# RTC6705.net
KiCad netlist of a schematic drawn in Altium Designer
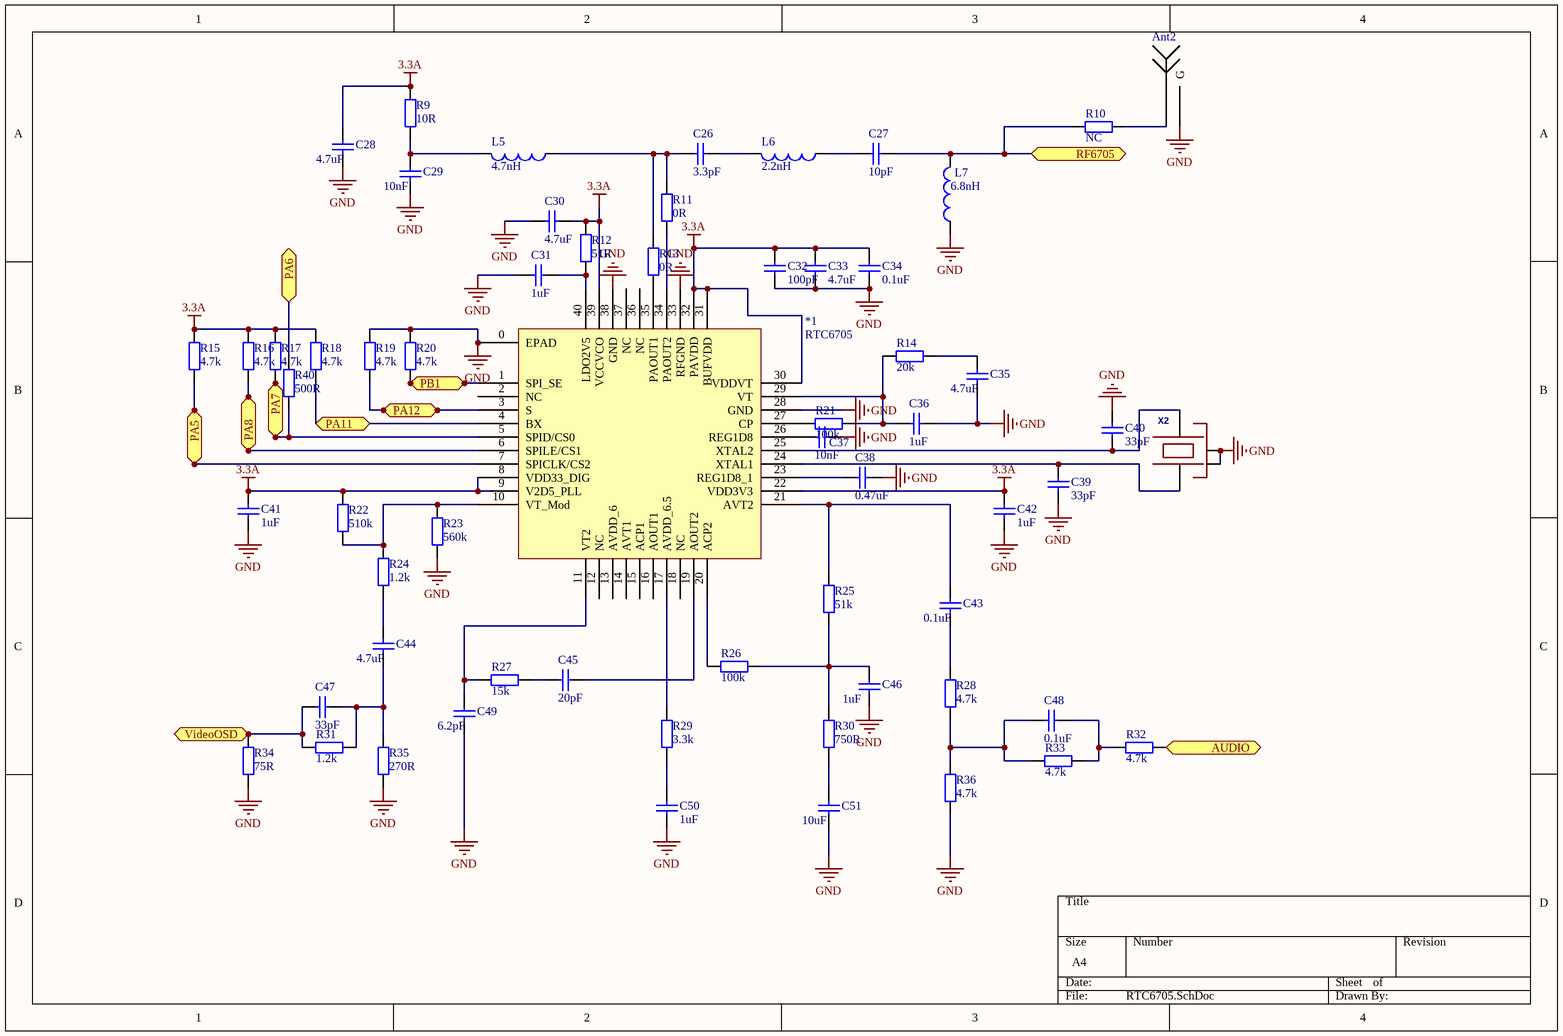
[diagram p0: RTC6705.SchDoc]

(export (version "E")
  (design (tool "Eeschema 10.0.6"))
  (components
    (comp (ref "*1") (value "RTC6705") (footprint "RTC6705") (libsource (lib "RTC6705") (part "RTC6705")))
    (comp (ref "Ant2") (value "Antenna") (footprint "SMA") (libsource (lib "RTC6705") (part "Antenna")))
    (comp (ref "C26")
      (value "3.3pF")
      (footprint "0402")
      (description "Capacitor")
      (fields (field (name "Comment") "Cap") (field (name "PUBLISHER") "Altium Limited"))
      (libsource (lib "RTC6705") (part "Cap"))
    )
    (comp (ref "C27")
      (value "10pF")
      (footprint "0402")
      (description "Capacitor")
      (fields (field (name "Comment") "Cap") (field (name "PUBLISHER") "Altium Limited"))
      (libsource (lib "RTC6705") (part "Cap"))
    )
    (comp (ref "C28")
      (value "4.7uF")
      (footprint "0603")
      (description "Capacitor")
      (fields (field (name "Comment") "Cap") (field (name "PUBLISHER") "Altium Limited"))
      (libsource (lib "RTC6705") (part "Cap"))
    )
    (comp (ref "C29")
      (value "10nF")
      (footprint "0402")
      (description "Capacitor")
      (fields (field (name "Comment") "Cap") (field (name "PUBLISHER") "Altium Limited"))
      (libsource (lib "RTC6705") (part "Cap"))
    )
    (comp (ref "C30")
      (value "4.7uF")
      (footprint "0402")
      (description "Capacitor")
      (fields (field (name "Comment") "Cap") (field (name "PUBLISHER") "Altium Limited"))
      (libsource (lib "RTC6705") (part "Cap"))
    )
    (comp (ref "C31")
      (value "1uF")
      (footprint "0402")
      (description "Capacitor")
      (fields (field (name "Comment") "Cap") (field (name "PUBLISHER") "Altium Limited"))
      (libsource (lib "RTC6705") (part "Cap"))
    )
    (comp (ref "C32")
      (value "100pF")
      (footprint "0402")
      (description "Capacitor")
      (fields (field (name "Comment") "Cap") (field (name "PUBLISHER") "Altium Limited"))
      (libsource (lib "RTC6705") (part "Cap"))
    )
    (comp (ref "C33")
      (value "4.7uF")
      (footprint "0402")
      (description "Capacitor")
      (fields (field (name "Comment") "Cap") (field (name "PUBLISHER") "Altium Limited"))
      (libsource (lib "RTC6705") (part "Cap"))
    )
    (comp (ref "C34")
      (value "0.1uF")
      (footprint "0402")
      (description "Capacitor")
      (fields (field (name "Comment") "Cap") (field (name "PUBLISHER") "Altium Limited"))
      (libsource (lib "RTC6705") (part "Cap"))
    )
    (comp (ref "C35")
      (value "4.7uF")
      (footprint "0402")
      (description "Capacitor")
      (fields (field (name "Comment") "Cap") (field (name "PUBLISHER") "Altium Limited"))
      (libsource (lib "RTC6705") (part "Cap"))
    )
    (comp (ref "C36")
      (value "1uF")
      (footprint "0402")
      (description "Capacitor")
      (fields (field (name "Comment") "Cap") (field (name "PUBLISHER") "Altium Limited"))
      (libsource (lib "RTC6705") (part "Cap"))
    )
    (comp (ref "C37")
      (value "10nF")
      (footprint "0402")
      (description "Capacitor")
      (fields (field (name "Comment") "Cap") (field (name "PUBLISHER") "Altium Limited"))
      (libsource (lib "RTC6705") (part "Cap"))
    )
    (comp (ref "C38")
      (value "0.47uF")
      (footprint "0402")
      (description "Capacitor")
      (fields (field (name "Comment") "Cap") (field (name "PUBLISHER") "Altium Limited"))
      (libsource (lib "RTC6705") (part "Cap"))
    )
    (comp (ref "C39")
      (value "33pF")
      (footprint "0402")
      (description "Capacitor")
      (fields (field (name "Comment") "Cap") (field (name "PUBLISHER") "Altium Limited"))
      (libsource (lib "RTC6705") (part "Cap"))
    )
    (comp (ref "C40")
      (value "33pF")
      (footprint "0402")
      (description "Capacitor")
      (fields (field (name "Comment") "Cap") (field (name "PUBLISHER") "Altium Limited"))
      (libsource (lib "RTC6705") (part "Cap"))
    )
    (comp (ref "C41")
      (value "1uF")
      (footprint "0402")
      (description "Capacitor")
      (fields (field (name "Comment") "Cap") (field (name "PUBLISHER") "Altium Limited"))
      (libsource (lib "RTC6705") (part "Cap"))
    )
    (comp (ref "C42")
      (value "1uF")
      (footprint "0402")
      (description "Capacitor")
      (fields (field (name "Comment") "Cap") (field (name "PUBLISHER") "Altium Limited"))
      (libsource (lib "RTC6705") (part "Cap"))
    )
    (comp (ref "C43")
      (value "0.1uF")
      (footprint "0402")
      (description "Capacitor")
      (fields (field (name "Comment") "Cap") (field (name "PUBLISHER") "Altium Limited"))
      (libsource (lib "RTC6705") (part "Cap"))
    )
    (comp (ref "C44")
      (value "4.7uF")
      (footprint "0402")
      (description "Capacitor")
      (fields (field (name "Comment") "Cap") (field (name "PUBLISHER") "Altium Limited"))
      (libsource (lib "RTC6705") (part "Cap"))
    )
    (comp (ref "C45")
      (value "20pF")
      (footprint "0402")
      (description "Capacitor")
      (fields (field (name "Comment") "Cap") (field (name "PUBLISHER") "Altium Limited"))
      (libsource (lib "RTC6705") (part "Cap"))
    )
    (comp (ref "C46")
      (value "1uF")
      (footprint "0402")
      (description "Capacitor")
      (fields (field (name "Comment") "Cap") (field (name "PUBLISHER") "Altium Limited"))
      (libsource (lib "RTC6705") (part "Cap"))
    )
    (comp (ref "C47")
      (value "33pF")
      (footprint "0402")
      (description "Capacitor")
      (fields (field (name "Comment") "Cap") (field (name "PUBLISHER") "Altium Limited"))
      (libsource (lib "RTC6705") (part "Cap"))
    )
    (comp (ref "C48")
      (value "0.1uF")
      (footprint "0402")
      (description "Capacitor")
      (fields (field (name "Comment") "Cap") (field (name "PUBLISHER") "Altium Limited"))
      (libsource (lib "RTC6705") (part "Cap"))
    )
    (comp (ref "C49")
      (value "6.2pF")
      (footprint "0402")
      (description "Capacitor")
      (fields (field (name "Comment") "Cap") (field (name "PUBLISHER") "Altium Limited"))
      (libsource (lib "RTC6705") (part "Cap"))
    )
    (comp (ref "C50")
      (value "1uF")
      (footprint "0402")
      (description "Capacitor")
      (fields (field (name "Comment") "Cap") (field (name "PUBLISHER") "Altium Limited"))
      (libsource (lib "RTC6705") (part "Cap"))
    )
    (comp (ref "C51")
      (value "10uF")
      (footprint "0402")
      (description "Capacitor")
      (fields (field (name "Comment") "Cap") (field (name "PUBLISHER") "Altium Limited"))
      (libsource (lib "RTC6705") (part "Cap"))
    )
    (comp (ref "L5")
      (value "4.7nH")
      (footprint "0402")
      (description "Inductor")
      (fields (field (name "PUBLISHER") "Altium Limited"))
      (libsource (lib "Miscellaneous Devices") (part "Inductor"))
    )
    (comp (ref "L6")
      (value "2.2nH")
      (footprint "0402")
      (description "Inductor")
      (fields (field (name "PUBLISHER") "Altium Limited"))
      (libsource (lib "Miscellaneous Devices") (part "Inductor"))
    )
    (comp (ref "L7")
      (value "6.8nH")
      (footprint "0402")
      (description "Inductor")
      (fields (field (name "PUBLISHER") "Altium Limited"))
      (libsource (lib "Miscellaneous Devices") (part "Inductor"))
    )
    (comp (ref "R9")
      (value "10R")
      (footprint "0402")
      (description "Resistor")
      (fields (field (name "Comment") "Res2") (field (name "PUBLISHER") "Altium Limited"))
      (libsource (lib "") (part "Res2_2"))
    )
    (comp (ref "R10")
      (value "NC")
      (footprint "0402")
      (description "Resistor")
      (fields (field (name "Comment") "Res2") (field (name "PUBLISHER") "Altium Limited"))
      (libsource (lib "") (part "Res2_1"))
    )
    (comp (ref "R11")
      (value "0R")
      (footprint "0402")
      (description "Resistor")
      (fields (field (name "Comment") "Res2") (field (name "PUBLISHER") "Altium Limited"))
      (libsource (lib "") (part "Res2_2"))
    )
    (comp (ref "R12")
      (value "51R")
      (footprint "0402")
      (description "Resistor")
      (fields (field (name "Comment") "Res2") (field (name "PUBLISHER") "Altium Limited"))
      (libsource (lib "") (part "Res2_2"))
    )
    (comp (ref "R13")
      (value "0R")
      (footprint "0402")
      (description "Resistor")
      (fields (field (name "Comment") "Res2") (field (name "PUBLISHER") "Altium Limited"))
      (libsource (lib "") (part "Res2_2"))
    )
    (comp (ref "R14")
      (value "20k")
      (footprint "0402")
      (description "Resistor")
      (fields (field (name "Comment") "Res2") (field (name "PUBLISHER") "Altium Limited"))
      (libsource (lib "") (part "Res2_1"))
    )
    (comp (ref "R15")
      (value "4.7k")
      (footprint "0402")
      (description "Resistor")
      (fields (field (name "Comment") "Res2") (field (name "PUBLISHER") "Altium Limited"))
      (libsource (lib "") (part "Res2_2"))
    )
    (comp (ref "R16")
      (value "4.7k")
      (footprint "0402")
      (description "Resistor")
      (fields (field (name "Comment") "Res2") (field (name "PUBLISHER") "Altium Limited"))
      (libsource (lib "") (part "Res2_2"))
    )
    (comp (ref "R17")
      (value "4.7k")
      (footprint "0402")
      (description "Resistor")
      (fields (field (name "Comment") "Res2") (field (name "PUBLISHER") "Altium Limited"))
      (libsource (lib "") (part "Res2_2"))
    )
    (comp (ref "R18")
      (value "4.7k")
      (footprint "0402")
      (description "Resistor")
      (fields (field (name "Comment") "Res2") (field (name "PUBLISHER") "Altium Limited"))
      (libsource (lib "") (part "Res2_2"))
    )
    (comp (ref "R19")
      (value "4.7k")
      (footprint "0402")
      (description "Resistor")
      (fields (field (name "Comment") "Res2") (field (name "PUBLISHER") "Altium Limited"))
      (libsource (lib "") (part "Res2_2"))
    )
    (comp (ref "R20")
      (value "4.7k")
      (footprint "0402")
      (description "Resistor")
      (fields (field (name "Comment") "Res2") (field (name "PUBLISHER") "Altium Limited"))
      (libsource (lib "") (part "Res2_2"))
    )
    (comp (ref "R21")
      (value "100k")
      (footprint "0402")
      (description "Resistor")
      (fields (field (name "Comment") "Res2") (field (name "PUBLISHER") "Altium Limited"))
      (libsource (lib "") (part "Res2_1"))
    )
    (comp (ref "R22")
      (value "510k")
      (footprint "0402")
      (description "Resistor")
      (fields (field (name "Comment") "Res2") (field (name "PUBLISHER") "Altium Limited"))
      (libsource (lib "") (part "Res2_2"))
    )
    (comp (ref "R23")
      (value "560k")
      (footprint "0402")
      (description "Resistor")
      (fields (field (name "Comment") "Res2") (field (name "PUBLISHER") "Altium Limited"))
      (libsource (lib "") (part "Res2_2"))
    )
    (comp (ref "R24")
      (value "1.2k")
      (footprint "0402")
      (description "Resistor")
      (fields (field (name "Comment") "Res2") (field (name "PUBLISHER") "Altium Limited"))
      (libsource (lib "") (part "Res2_2"))
    )
    (comp (ref "R25")
      (value "51k")
      (footprint "0402")
      (description "Resistor")
      (fields (field (name "Comment") "Res2") (field (name "PUBLISHER") "Altium Limited"))
      (libsource (lib "") (part "Res2_2"))
    )
    (comp (ref "R26")
      (value "100k")
      (footprint "0402")
      (description "Resistor")
      (fields (field (name "Comment") "Res2") (field (name "PUBLISHER") "Altium Limited"))
      (libsource (lib "") (part "Res2_1"))
    )
    (comp (ref "R27")
      (value "15k")
      (footprint "0402")
      (description "Resistor")
      (fields (field (name "Comment") "Res2") (field (name "PUBLISHER") "Altium Limited"))
      (libsource (lib "") (part "Res2_1"))
    )
    (comp (ref "R28")
      (value "4.7k")
      (footprint "0402")
      (description "Resistor")
      (fields (field (name "Comment") "Res2") (field (name "PUBLISHER") "Altium Limited"))
      (libsource (lib "") (part "Res2_2"))
    )
    (comp (ref "R29")
      (value "3.3k")
      (footprint "0402")
      (description "Resistor")
      (fields (field (name "Comment") "Res2") (field (name "PUBLISHER") "Altium Limited"))
      (libsource (lib "RTC6705") (part "Res2"))
    )
    (comp (ref "R30")
      (value "750R")
      (footprint "0402")
      (description "Resistor")
      (fields (field (name "Comment") "Res2") (field (name "PUBLISHER") "Altium Limited"))
      (libsource (lib "") (part "Res2_2"))
    )
    (comp (ref "R31")
      (value "1.2k")
      (footprint "0402")
      (description "Resistor")
      (fields (field (name "Comment") "Res2") (field (name "PUBLISHER") "Altium Limited"))
      (libsource (lib "") (part "Res2_1"))
    )
    (comp (ref "R32")
      (value "4.7k")
      (footprint "0402")
      (description "Resistor")
      (fields (field (name "Comment") "Res2") (field (name "PUBLISHER") "Altium Limited"))
      (libsource (lib "") (part "Res2_1"))
    )
    (comp (ref "R33")
      (value "4.7k")
      (footprint "0402")
      (description "Resistor")
      (fields (field (name "Comment") "Res2") (field (name "PUBLISHER") "Altium Limited"))
      (libsource (lib "") (part "Res2_1"))
    )
    (comp (ref "R34")
      (value "75R")
      (footprint "0402")
      (description "Resistor")
      (fields (field (name "Comment") "Res2") (field (name "PUBLISHER") "Altium Limited"))
      (libsource (lib "") (part "Res2_2"))
    )
    (comp (ref "R35")
      (value "270R")
      (footprint "0402")
      (description "Resistor")
      (fields (field (name "Comment") "Res2") (field (name "PUBLISHER") "Altium Limited"))
      (libsource (lib "") (part "Res2_2"))
    )
    (comp (ref "R36")
      (value "4.7k")
      (footprint "0402")
      (description "Resistor")
      (fields (field (name "Comment") "Res2") (field (name "PUBLISHER") "Altium Limited"))
      (libsource (lib "") (part "Res2_2"))
    )
    (comp (ref "R40")
      (value "500R")
      (footprint "0402")
      (description "Resistor")
      (fields (field (name "Comment") "Res2") (field (name "PUBLISHER") "Altium Limited"))
      (libsource (lib "") (part "Res2_2"))
    )
    (comp (ref "X2")
      (value "8mhz")
      (footprint "OSCILLATOR-3.2X2.5")
      (description "Crystal Oscillator in 3.2x2.5 SMD")
      (libsource (lib "pixhawk2") (part "OSCILLATOR-3.2X2.5"))
    )
  )
  (nets
    (net (code "1") (name "/AUDIO") (class "Default")
      (node (ref "R32") (pin "1") (pinfunction "1_1") (pintype "passive"))
    )
    (net (code "2") (name "/PA5") (class "Default")
      (node (ref "*1") (pin "7") (pinfunction "SPICLK/CS2_7") (pintype "passive"))
      (node (ref "R15") (pin "1") (pinfunction "1_1") (pintype "passive"))
    )
    (net (code "3") (name "/PA6") (class "Default")
      (node (ref "R40") (pin "2") (pinfunction "2_2") (pintype "passive"))
    )
    (net (code "4") (name "/PA7") (class "Default")
      (node (ref "*1") (pin "5") (pinfunction "SPID/CS0_5") (pintype "passive"))
      (node (ref "R17") (pin "1") (pinfunction "1_1") (pintype "passive"))
      (node (ref "R40") (pin "1") (pinfunction "1_1") (pintype "passive"))
    )
    (net (code "5") (name "/PA8") (class "Default")
      (node (ref "*1") (pin "6") (pinfunction "SPILE/CS1_6") (pintype "passive"))
      (node (ref "R16") (pin "1") (pinfunction "1_1") (pintype "passive"))
    )
    (net (code "6") (name "/PA11") (class "Default")
      (node (ref "*1") (pin "4") (pinfunction "BX_4") (pintype "passive"))
      (node (ref "R18") (pin "1") (pinfunction "1_1") (pintype "passive"))
    )
    (net (code "7") (name "/PA12") (class "Default")
      (node (ref "*1") (pin "3") (pinfunction "S_3") (pintype "passive"))
      (node (ref "R19") (pin "1") (pinfunction "1_1") (pintype "passive"))
    )
    (net (code "8") (name "/PB1") (class "Default")
      (node (ref "*1") (pin "1") (pinfunction "SPI_SE_1") (pintype "passive"))
      (node (ref "R20") (pin "1") (pinfunction "1_1") (pintype "passive"))
    )
    (net (code "9") (name "/RF6705") (class "Default")
      (node (ref "C27") (pin "1") (pinfunction "1_1") (pintype "passive"))
      (node (ref "L7") (pin "2") (pinfunction "2_2") (pintype "passive"))
      (node (ref "R10") (pin "2") (pinfunction "2_2") (pintype "passive"))
    )
    (net (code "10") (name "/VideoOSD") (class "Default")
      (node (ref "C47") (pin "2") (pinfunction "2_2") (pintype "passive"))
      (node (ref "R31") (pin "2") (pinfunction "2_2") (pintype "passive"))
      (node (ref "R34") (pin "2") (pinfunction "2_2") (pintype "passive"))
    )
    (net (code "11") (name "3.3A") (class "Default")
      (node (ref "*1") (pin "22") (pinfunction "VDD3V3_22") (pintype "passive"))
      (node (ref "*1") (pin "30") (pinfunction "VDDVT_30") (pintype "passive"))
      (node (ref "*1") (pin "31") (pinfunction "BUFVDD_31") (pintype "passive"))
      (node (ref "*1") (pin "32") (pinfunction "PAVDD_32") (pintype "passive"))
      (node (ref "*1") (pin "39") (pinfunction "VCCVCO_39") (pintype "passive"))
      (node (ref "*1") (pin "8") (pinfunction "VDD33_DIG_8") (pintype "passive"))
      (node (ref "*1") (pin "9") (pinfunction "V2D5_PLL_9") (pintype "passive"))
      (node (ref "C28") (pin "2") (pinfunction "2_2") (pintype "passive"))
      (node (ref "C30") (pin "2") (pinfunction "2_2") (pintype "passive"))
      (node (ref "C32") (pin "1") (pinfunction "1_1") (pintype "passive"))
      (node (ref "C33") (pin "1") (pinfunction "1_1") (pintype "passive"))
      (node (ref "C34") (pin "1") (pinfunction "1_1") (pintype "passive"))
      (node (ref "C41") (pin "1") (pinfunction "1_1") (pintype "passive"))
      (node (ref "C42") (pin "1") (pinfunction "1_1") (pintype "passive"))
      (node (ref "R12") (pin "2") (pinfunction "2_2") (pintype "passive"))
      (node (ref "R15") (pin "2") (pinfunction "2_2") (pintype "passive"))
      (node (ref "R16") (pin "2") (pinfunction "2_2") (pintype "passive"))
      (node (ref "R17") (pin "2") (pinfunction "2_2") (pintype "passive"))
      (node (ref "R18") (pin "2") (pinfunction "2_2") (pintype "passive"))
      (node (ref "R22") (pin "2") (pinfunction "2_2") (pintype "passive"))
      (node (ref "R9") (pin "2") (pinfunction "2_2") (pintype "passive"))
    )
    (net (code "12") (name "GND") (class "Default")
      (node (ref "*1") (pin "0") (pinfunction "EPAD_0") (pintype "passive"))
      (node (ref "*1") (pin "28") (pinfunction "GND_28") (pintype "passive"))
      (node (ref "*1") (pin "33") (pinfunction "RFGND_33") (pintype "passive"))
      (node (ref "*1") (pin "38") (pinfunction "GND_38") (pintype "passive"))
      (node (ref "Ant2") (pin "GND") (pinfunction "G_GND") (pintype "passive"))
      (node (ref "C28") (pin "1") (pinfunction "1_1") (pintype "passive"))
      (node (ref "C29") (pin "1") (pinfunction "1_1") (pintype "passive"))
      (node (ref "C30") (pin "1") (pinfunction "1_1") (pintype "passive"))
      (node (ref "C31") (pin "2") (pinfunction "2_2") (pintype "passive"))
      (node (ref "C32") (pin "2") (pinfunction "2_2") (pintype "passive"))
      (node (ref "C33") (pin "2") (pinfunction "2_2") (pintype "passive"))
      (node (ref "C34") (pin "2") (pinfunction "2_2") (pintype "passive"))
      (node (ref "C35") (pin "1") (pinfunction "1_1") (pintype "passive"))
      (node (ref "C36") (pin "1") (pinfunction "1_1") (pintype "passive"))
      (node (ref "C37") (pin "1") (pinfunction "1_1") (pintype "passive"))
      (node (ref "C38") (pin "1") (pinfunction "1_1") (pintype "passive"))
      (node (ref "C39") (pin "2") (pinfunction "2_2") (pintype "passive"))
      (node (ref "C40") (pin "2") (pinfunction "2_2") (pintype "passive"))
      (node (ref "C41") (pin "2") (pinfunction "2_2") (pintype "passive"))
      (node (ref "C42") (pin "2") (pinfunction "2_2") (pintype "passive"))
      (node (ref "C46") (pin "1") (pinfunction "1_1") (pintype "passive"))
      (node (ref "C49") (pin "1") (pinfunction "1_1") (pintype "passive"))
      (node (ref "C50") (pin "2") (pinfunction "2_2") (pintype "passive"))
      (node (ref "C51") (pin "1") (pinfunction "1_1") (pintype "passive"))
      (node (ref "L7") (pin "1") (pinfunction "1_1") (pintype "passive"))
      (node (ref "R19") (pin "2") (pinfunction "2_2") (pintype "passive"))
      (node (ref "R20") (pin "2") (pinfunction "2_2") (pintype "passive"))
      (node (ref "R23") (pin "1") (pinfunction "1_1") (pintype "passive"))
      (node (ref "R34") (pin "1") (pinfunction "1_1") (pintype "passive"))
      (node (ref "R35") (pin "1") (pinfunction "1_1") (pintype "passive"))
      (node (ref "R36") (pin "1") (pinfunction "1_1") (pintype "passive"))
      (node (ref "X2") (pin "2") (pinfunction "NC_2_2") (pintype "open_emitter"))
      (node (ref "X2") (pin "4") (pinfunction "NC_4_4") (pintype "open_emitter"))
    )
    (net (code "13") (name "Net-(*1-ACP2)") (class "Default")
      (node (ref "*1") (pin "20") (pinfunction "ACP2_20") (pintype "passive"))
      (node (ref "R26") (pin "2") (pinfunction "2_2") (pintype "passive"))
    )
    (net (code "14") (name "Net-(*1-AOUT2)") (class "Default")
      (node (ref "*1") (pin "19") (pinfunction "AOUT2_19") (pintype "passive"))
      (node (ref "C45") (pin "1") (pinfunction "1_1") (pintype "passive"))
    )
    (net (code "15") (name "Net-(*1-AVDD_6.5)") (class "Default")
      (node (ref "*1") (pin "17") (pinfunction "AVDD_6.5_17") (pintype "passive"))
      (node (ref "R29") (pin "1") (pinfunction "1_1") (pintype "passive"))
    )
    (net (code "16") (name "Net-(*1-AVT2)") (class "Default")
      (node (ref "*1") (pin "21") (pinfunction "AVT2_21") (pintype "passive"))
      (node (ref "C43") (pin "2") (pinfunction "2_2") (pintype "passive"))
      (node (ref "R25") (pin "2") (pinfunction "2_2") (pintype "passive"))
    )
    (net (code "17") (name "Net-(*1-CP)") (class "Default")
      (node (ref "*1") (pin "27") (pinfunction "CP_27") (pintype "passive"))
      (node (ref "R21") (pin "2") (pinfunction "2_2") (pintype "passive"))
    )
    (net (code "18") (name "Net-(*1-LDO2V5)") (class "Default")
      (node (ref "*1") (pin "40") (pinfunction "LDO2V5_40") (pintype "passive"))
      (node (ref "C31") (pin "1") (pinfunction "1_1") (pintype "passive"))
      (node (ref "R12") (pin "1") (pinfunction "1_1") (pintype "passive"))
    )
    (net (code "19") (name "Net-(*1-PAOUT1)") (class "Default")
      (node (ref "*1") (pin "35") (pinfunction "PAOUT1_35") (pintype "passive"))
      (node (ref "R13") (pin "1") (pinfunction "1_1") (pintype "passive"))
    )
    (net (code "20") (name "Net-(*1-PAOUT2)") (class "Default")
      (node (ref "*1") (pin "34") (pinfunction "PAOUT2_34") (pintype "passive"))
      (node (ref "R11") (pin "1") (pinfunction "1_1") (pintype "passive"))
    )
    (net (code "21") (name "Net-(*1-REG1D8)") (class "Default")
      (node (ref "*1") (pin "26") (pinfunction "REG1D8_26") (pintype "passive"))
      (node (ref "C37") (pin "2") (pinfunction "2_2") (pintype "passive"))
    )
    (net (code "22") (name "Net-(*1-REG1D8_1)") (class "Default")
      (node (ref "*1") (pin "23") (pinfunction "REG1D8_1_23") (pintype "passive"))
      (node (ref "C38") (pin "2") (pinfunction "2_2") (pintype "passive"))
    )
    (net (code "23") (name "Net-(*1-VT)") (class "Default")
      (node (ref "*1") (pin "29") (pinfunction "VT_29") (pintype "passive"))
      (node (ref "C36") (pin "2") (pinfunction "2_2") (pintype "passive"))
      (node (ref "R14") (pin "2") (pinfunction "2_2") (pintype "passive"))
      (node (ref "R21") (pin "1") (pinfunction "1_1") (pintype "passive"))
    )
    (net (code "24") (name "Net-(*1-VT2)") (class "Default")
      (node (ref "*1") (pin "11") (pinfunction "VT2_11") (pintype "passive"))
      (node (ref "C49") (pin "2") (pinfunction "2_2") (pintype "passive"))
      (node (ref "R27") (pin "2") (pinfunction "2_2") (pintype "passive"))
    )
    (net (code "25") (name "Net-(*1-VT_Mod)") (class "Default")
      (node (ref "*1") (pin "10") (pinfunction "VT_Mod_10") (pintype "passive"))
      (node (ref "R22") (pin "1") (pinfunction "1_1") (pintype "passive"))
      (node (ref "R23") (pin "2") (pinfunction "2_2") (pintype "passive"))
      (node (ref "R24") (pin "2") (pinfunction "2_2") (pintype "passive"))
    )
    (net (code "26") (name "Net-(*1-XTAL1)") (class "Default")
      (node (ref "*1") (pin "24") (pinfunction "XTAL1_24") (pintype "passive"))
      (node (ref "C39") (pin "1") (pinfunction "1_1") (pintype "passive"))
      (node (ref "X2") (pin "1") (pinfunction "1_1") (pintype "passive"))
    )
    (net (code "27") (name "Net-(*1-XTAL2)") (class "Default")
      (node (ref "*1") (pin "25") (pinfunction "XTAL2_25") (pintype "passive"))
      (node (ref "C40") (pin "1") (pinfunction "1_1") (pintype "passive"))
      (node (ref "X2") (pin "3") (pinfunction "3_3") (pintype "passive"))
    )
    (net (code "28") (name "Net-(Ant2-Pad1)") (class "Default")
      (node (ref "Ant2") (pin "1") (pinfunction "1_1") (pintype "passive"))
      (node (ref "R10") (pin "1") (pinfunction "1_1") (pintype "passive"))
    )
    (net (code "29") (name "Net-(C26-Pad1)") (class "Default")
      (node (ref "C26") (pin "1") (pinfunction "1_1") (pintype "passive"))
      (node (ref "L6") (pin "2") (pinfunction "2_2") (pintype "passive"))
    )
    (net (code "30") (name "Net-(C26-Pad2)") (class "Default")
      (node (ref "C26") (pin "2") (pinfunction "2_2") (pintype "passive"))
      (node (ref "L5") (pin "1") (pinfunction "1_1") (pintype "passive"))
      (node (ref "R11") (pin "2") (pinfunction "2_2") (pintype "passive"))
      (node (ref "R13") (pin "2") (pinfunction "2_2") (pintype "passive"))
    )
    (net (code "31") (name "Net-(C27-Pad2)") (class "Default")
      (node (ref "C27") (pin "2") (pinfunction "2_2") (pintype "passive"))
      (node (ref "L6") (pin "1") (pinfunction "1_1") (pintype "passive"))
    )
    (net (code "32") (name "Net-(C29-Pad2)") (class "Default")
      (node (ref "C29") (pin "2") (pinfunction "2_2") (pintype "passive"))
      (node (ref "L5") (pin "2") (pinfunction "2_2") (pintype "passive"))
      (node (ref "R9") (pin "1") (pinfunction "1_1") (pintype "passive"))
    )
    (net (code "33") (name "Net-(C35-Pad2)") (class "Default")
      (node (ref "C35") (pin "2") (pinfunction "2_2") (pintype "passive"))
      (node (ref "R14") (pin "1") (pinfunction "1_1") (pintype "passive"))
    )
    (net (code "34") (name "Net-(C43-Pad1)") (class "Default")
      (node (ref "C43") (pin "1") (pinfunction "1_1") (pintype "passive"))
      (node (ref "R28") (pin "2") (pinfunction "2_2") (pintype "passive"))
    )
    (net (code "35") (name "Net-(C44-Pad1)") (class "Default")
      (node (ref "C44") (pin "1") (pinfunction "1_1") (pintype "passive"))
      (node (ref "C47") (pin "1") (pinfunction "1_1") (pintype "passive"))
      (node (ref "R31") (pin "1") (pinfunction "1_1") (pintype "passive"))
      (node (ref "R35") (pin "2") (pinfunction "2_2") (pintype "passive"))
    )
    (net (code "36") (name "Net-(C44-Pad2)") (class "Default")
      (node (ref "C44") (pin "2") (pinfunction "2_2") (pintype "passive"))
      (node (ref "R24") (pin "1") (pinfunction "1_1") (pintype "passive"))
    )
    (net (code "37") (name "Net-(C45-Pad2)") (class "Default")
      (node (ref "C45") (pin "2") (pinfunction "2_2") (pintype "passive"))
      (node (ref "R27") (pin "1") (pinfunction "1_1") (pintype "passive"))
    )
    (net (code "38") (name "Net-(C46-Pad2)") (class "Default")
      (node (ref "C46") (pin "2") (pinfunction "2_2") (pintype "passive"))
      (node (ref "R25") (pin "1") (pinfunction "1_1") (pintype "passive"))
      (node (ref "R26") (pin "1") (pinfunction "1_1") (pintype "passive"))
      (node (ref "R30") (pin "2") (pinfunction "2_2") (pintype "passive"))
    )
    (net (code "39") (name "Net-(C48-Pad1)") (class "Default")
      (node (ref "C48") (pin "1") (pinfunction "1_1") (pintype "passive"))
      (node (ref "R32") (pin "2") (pinfunction "2_2") (pintype "passive"))
      (node (ref "R33") (pin "1") (pinfunction "1_1") (pintype "passive"))
    )
    (net (code "40") (name "Net-(C48-Pad2)") (class "Default")
      (node (ref "C48") (pin "2") (pinfunction "2_2") (pintype "passive"))
      (node (ref "R28") (pin "1") (pinfunction "1_1") (pintype "passive"))
      (node (ref "R33") (pin "2") (pinfunction "2_2") (pintype "passive"))
      (node (ref "R36") (pin "2") (pinfunction "2_2") (pintype "passive"))
    )
    (net (code "41") (name "Net-(C50-Pad1)") (class "Default")
      (node (ref "C50") (pin "1") (pinfunction "1_1") (pintype "passive"))
      (node (ref "R29") (pin "2") (pinfunction "2_2") (pintype "passive"))
    )
    (net (code "42") (name "Net-(C51-Pad2)") (class "Default")
      (node (ref "C51") (pin "2") (pinfunction "2_2") (pintype "passive"))
      (node (ref "R30") (pin "1") (pinfunction "1_1") (pintype "passive"))
    )
    (net (code "43") (name "unconnected-(*1-ACP1-Pad15)") (class "Default")
      (node (ref "*1") (pin "15") (pinfunction "ACP1_15") (pintype "passive"))
    )
    (net (code "44") (name "unconnected-(*1-AOUT1-Pad16)") (class "Default")
      (node (ref "*1") (pin "16") (pinfunction "AOUT1_16") (pintype "passive"))
    )
    (net (code "45") (name "unconnected-(*1-AVDD_6-Pad13)") (class "Default")
      (node (ref "*1") (pin "13") (pinfunction "AVDD_6_13") (pintype "passive"))
    )
    (net (code "46") (name "unconnected-(*1-AVT1-Pad14)") (class "Default")
      (node (ref "*1") (pin "14") (pinfunction "AVT1_14") (pintype "passive"))
    )
    (net (code "47") (name "unconnected-(*1-NC-Pad2)") (class "Default")
      (node (ref "*1") (pin "2") (pinfunction "NC_2") (pintype "passive"))
    )
    (net (code "48") (name "unconnected-(*1-NC-Pad12)") (class "Default")
      (node (ref "*1") (pin "12") (pinfunction "NC_12") (pintype "passive"))
    )
    (net (code "49") (name "unconnected-(*1-NC-Pad18)") (class "Default")
      (node (ref "*1") (pin "18") (pinfunction "NC_18") (pintype "passive"))
    )
    (net (code "50") (name "unconnected-(*1-NC-Pad36)") (class "Default")
      (node (ref "*1") (pin "36") (pinfunction "NC_36") (pintype "passive"))
    )
    (net (code "51") (name "unconnected-(*1-NC-Pad37)") (class "Default")
      (node (ref "*1") (pin "37") (pinfunction "NC_37") (pintype "passive"))
    )
  )
)
